# Logomatic-v23.net
KiCad netlist of a schematic drawn in EAGLE
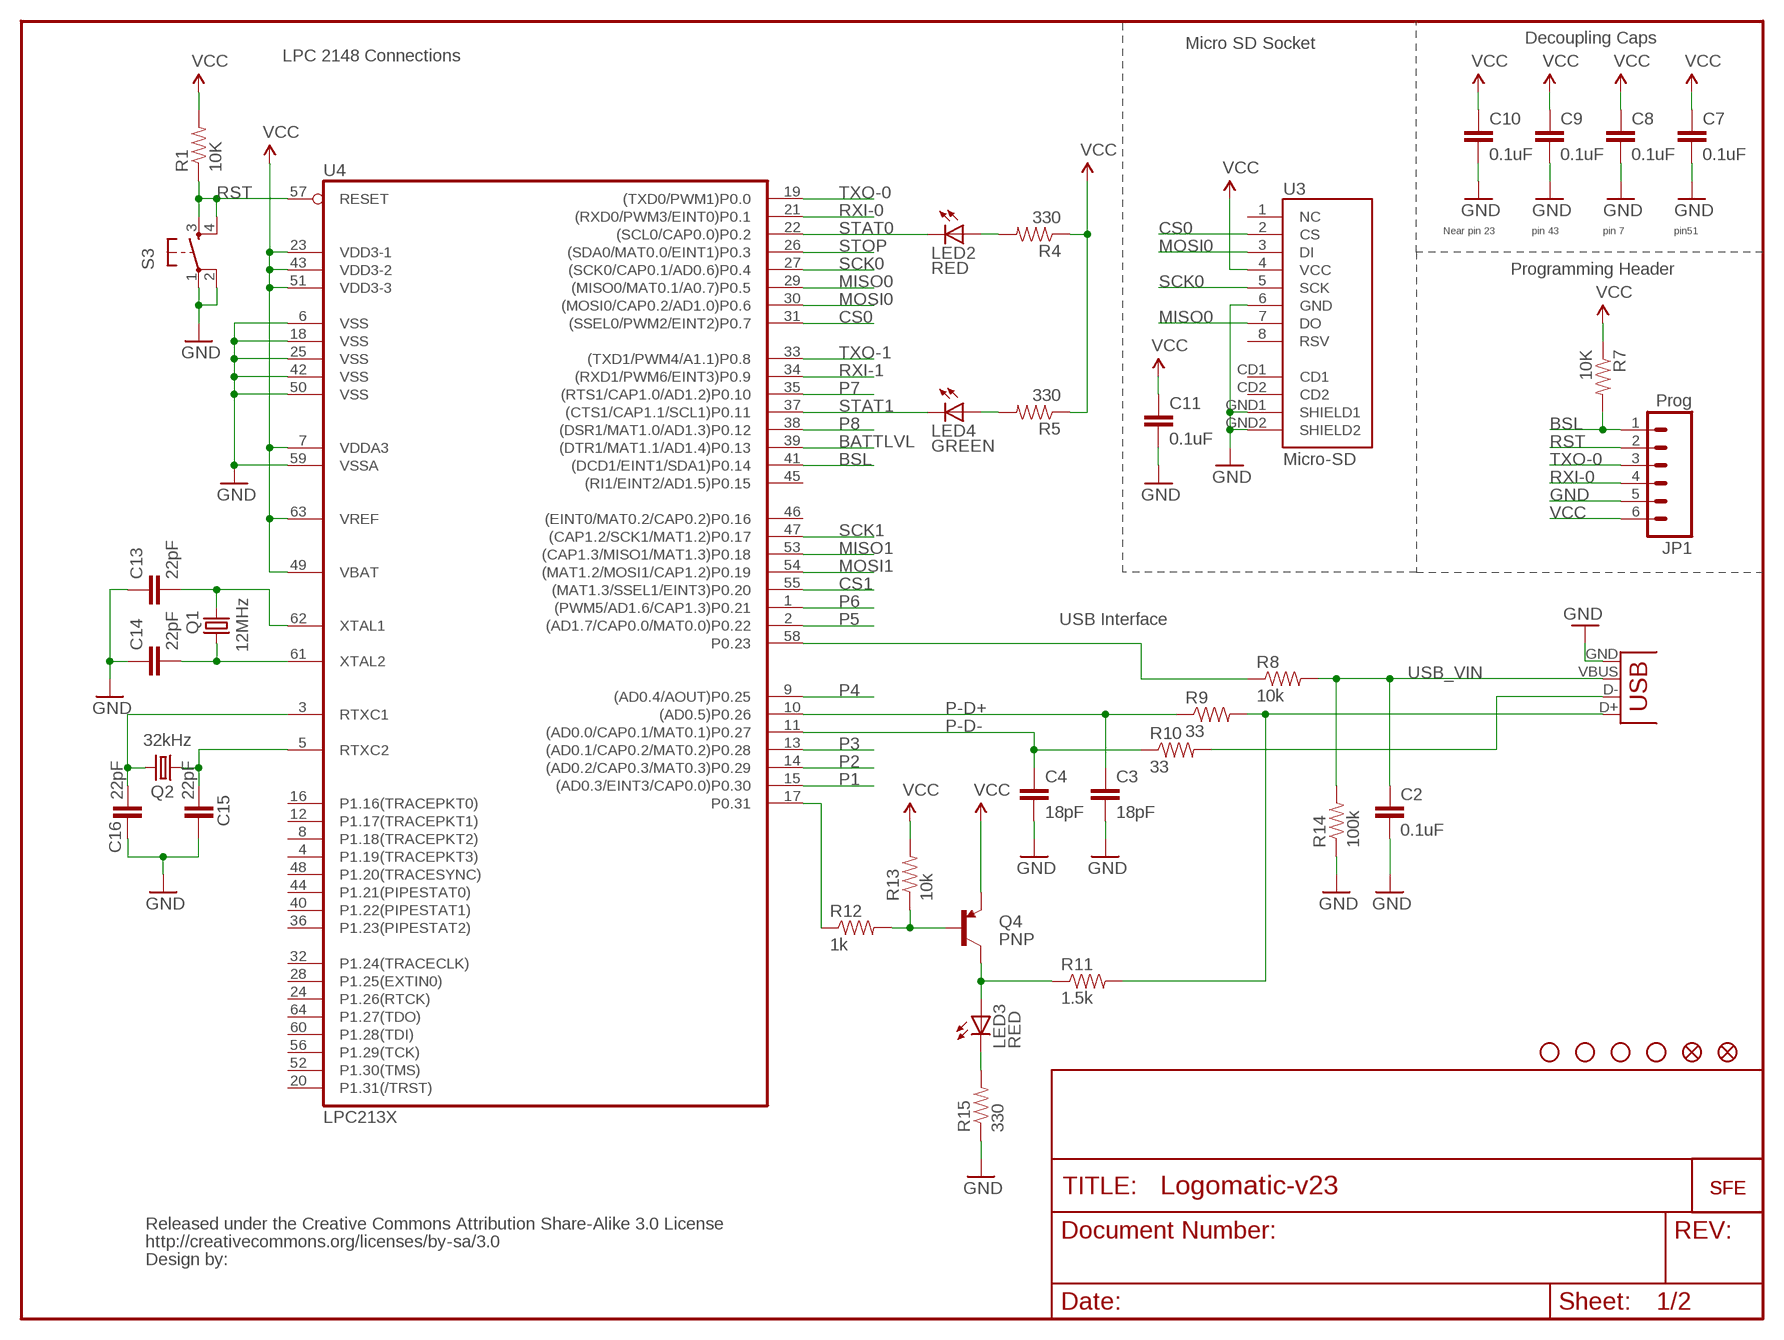
[diagram p0: schematic, sheet 1]
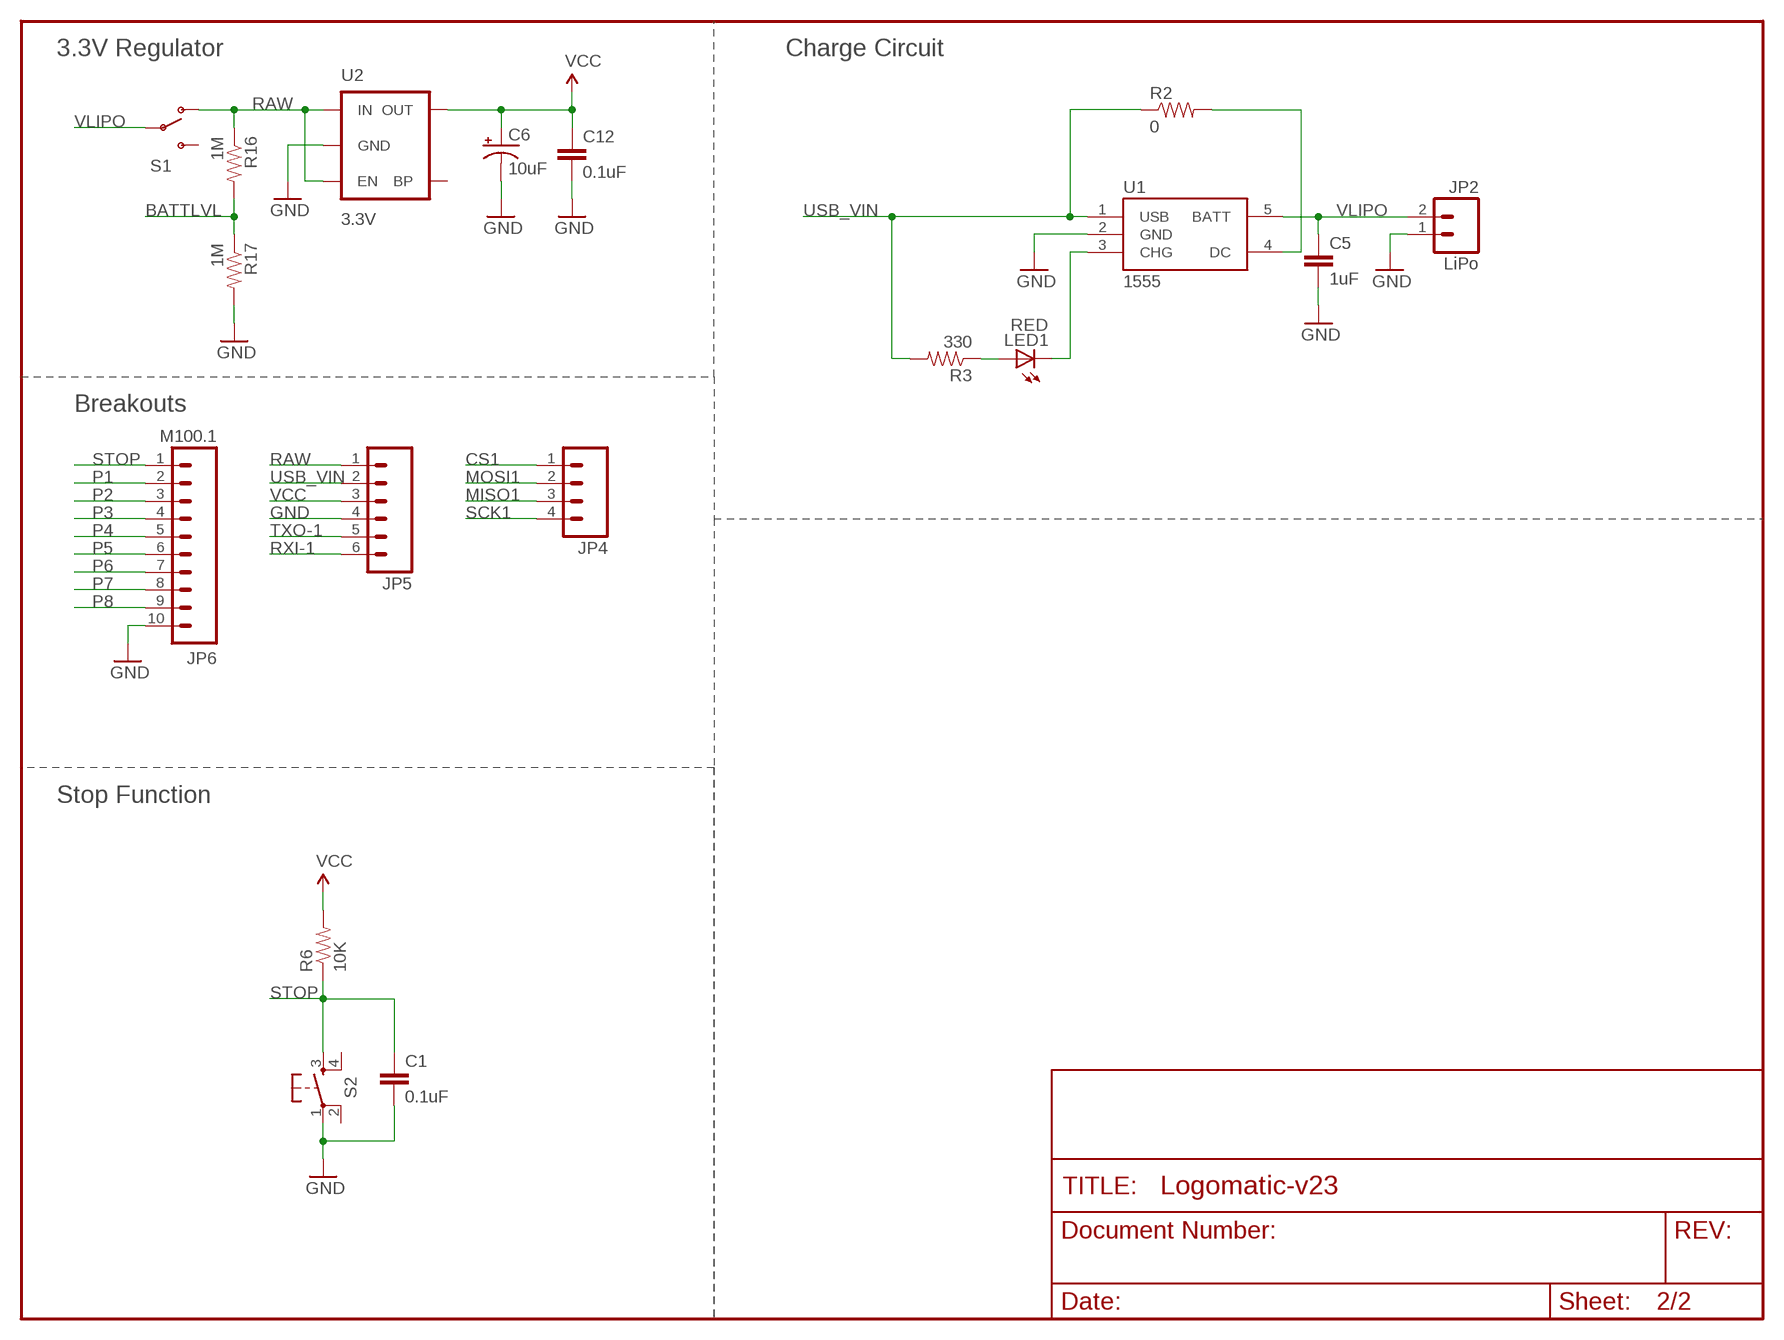
[diagram p1: schematic, sheet 2]

(export (version "E")
  (design (tool "Eeschema 10.0.6"))
  (components
    (comp (ref "C2")
      (value "0.1uF")
      (footprint "eagle-import:C0402")
      (libsource (lib "eagle-import") (part "SparkFunEagle-6-6-07_CAP0402"))
    )
    (comp (ref "C3")
      (value "18pF")
      (footprint "eagle-import:C0402")
      (libsource (lib "eagle-import") (part "SparkFunEagle-6-6-07_CAP0402"))
    )
    (comp (ref "C4")
      (value "18pF")
      (footprint "eagle-import:C0402")
      (libsource (lib "eagle-import") (part "SparkFunEagle-6-6-07_CAP0402"))
    )
    (comp (ref "C7")
      (value "0.1uF")
      (footprint "eagle-import:C0402")
      (libsource (lib "eagle-import") (part "SparkFunEagle-6-6-07_CAP0402"))
    )
    (comp (ref "C8")
      (value "0.1uF")
      (footprint "eagle-import:C0402")
      (libsource (lib "eagle-import") (part "SparkFunEagle-6-6-07_CAP0402"))
    )
    (comp (ref "C9")
      (value "0.1uF")
      (footprint "eagle-import:C0402")
      (libsource (lib "eagle-import") (part "SparkFunEagle-6-6-07_CAP0402"))
    )
    (comp (ref "C10")
      (value "0.1uF")
      (footprint "eagle-import:C0402")
      (libsource (lib "eagle-import") (part "SparkFunEagle-6-6-07_CAP0402"))
    )
    (comp (ref "C11")
      (value "0.1uF")
      (footprint "eagle-import:C0402")
      (libsource (lib "eagle-import") (part "SparkFunEagle-6-6-07_CAP0402"))
    )
    (comp (ref "C13")
      (value "22pF")
      (footprint "eagle-import:C0402")
      (libsource (lib "eagle-import") (part "SparkFunEagle-6-6-07_CAP0402"))
    )
    (comp (ref "C14")
      (value "22pF")
      (footprint "eagle-import:C0402")
      (libsource (lib "eagle-import") (part "SparkFunEagle-6-6-07_CAP0402"))
    )
    (comp (ref "C15")
      (value "22pF")
      (footprint "eagle-import:C0402")
      (libsource (lib "eagle-import") (part "SparkFunEagle-6-6-07_CAP0402"))
    )
    (comp (ref "C16")
      (value "22pF")
      (footprint "eagle-import:C0402")
      (libsource (lib "eagle-import") (part "SparkFunEagle-6-6-07_CAP0402"))
    )
    (comp (ref "JP1")
      (value "Prog")
      (footprint "eagle-import:1X06")
      (libsource (lib "eagle-import") (part "M06SIP"))
    )
    (comp (ref "LED2")
      (value "RED")
      (footprint "eagle-import:LED-0603")
      (libsource (lib "eagle-import") (part "SparkFunEagle-6-6-07_LED0603"))
    )
    (comp (ref "LED3")
      (value "RED")
      (footprint "eagle-import:LED-0603")
      (libsource (lib "eagle-import") (part "SparkFun_Master_LED0603"))
    )
    (comp (ref "LED4")
      (value "GREEN")
      (footprint "eagle-import:LED-0603")
      (libsource (lib "eagle-import") (part "SparkFunEagle-6-6-07_LED0603"))
    )
    (comp (ref "Q1")
      (value "12MHz")
      (footprint "eagle-import:CRYSTAL-SMD-5X3")
      (libsource (lib "eagle-import") (part "SparkFunEagle-6-6-07_CRYSTAL5X3"))
    )
    (comp (ref "Q2")
      (value "32kHz")
      (footprint "eagle-import:CRYSTAL-32KHZ-SMD")
      (libsource (lib "eagle-import") (part "CRYSTAL32-SMD"))
    )
    (comp (ref "Q4")
      (value "PNP")
      (footprint "eagle-import:SOT23-3")
      (libsource (lib "eagle-import") (part "TRANSISTOR_PNPSMD"))
    )
    (comp (ref "R1")
      (value "10K")
      (footprint "eagle-import:C0402")
      (libsource (lib "eagle-import") (part "SparkFunEagle-6-6-07_RESISTOR0402"))
    )
    (comp (ref "R4")
      (value "330")
      (footprint "eagle-import:C0402")
      (libsource (lib "eagle-import") (part "SparkFunEagle-6-6-07_RESISTOR0402"))
    )
    (comp (ref "R5")
      (value "330")
      (footprint "eagle-import:C0402")
      (libsource (lib "eagle-import") (part "SparkFunEagle-6-6-07_RESISTOR0402"))
    )
    (comp (ref "R7")
      (value "10K")
      (footprint "eagle-import:C0402")
      (libsource (lib "eagle-import") (part "SparkFunEagle-6-6-07_RESISTOR0402"))
    )
    (comp (ref "R8")
      (value "10k")
      (footprint "eagle-import:C0402")
      (libsource (lib "eagle-import") (part "SparkFunEagle-6-6-07_RESISTOR0402"))
    )
    (comp (ref "R9")
      (value "33")
      (footprint "eagle-import:C0402")
      (libsource (lib "eagle-import") (part "SparkFunEagle-6-6-07_RESISTOR0402"))
    )
    (comp (ref "R10")
      (value "33")
      (footprint "eagle-import:C0402")
      (libsource (lib "eagle-import") (part "SparkFunEagle-6-6-07_RESISTOR0402"))
    )
    (comp (ref "R11")
      (value "1.5k")
      (footprint "eagle-import:C0402")
      (libsource (lib "eagle-import") (part "SparkFunEagle-6-6-07_RESISTOR0402"))
    )
    (comp (ref "R12")
      (value "1k")
      (footprint "eagle-import:C0402")
      (libsource (lib "eagle-import") (part "SparkFunEagle-6-6-07_RESISTOR0402"))
    )
    (comp (ref "R13")
      (value "10k")
      (footprint "eagle-import:C0402")
      (libsource (lib "eagle-import") (part "SparkFunEagle-6-6-07_RESISTOR0402"))
    )
    (comp (ref "R14")
      (value "100k")
      (footprint "eagle-import:C0402")
      (libsource (lib "eagle-import") (part "SparkFunEagle-6-6-07_RESISTOR0402"))
    )
    (comp (ref "R15")
      (value "330")
      (footprint "eagle-import:C0402")
      (libsource (lib "eagle-import") (part "SparkFunEagle-6-6-07_RESISTOR0402"))
    )
    (comp (ref "S3")
      (value "Reset")
      (footprint "eagle-import:TACTILE_SWITCH_SMD")
      (libsource (lib "eagle-import") (part "TAC_SWITCHSND"))
    )
    (comp (ref "U$1")
      (value "FIDUCIAL1X2")
      (footprint "eagle-import:FIDUCIAL-1X2")
      (libsource (lib "eagle-import") (part "FIDUCIAL1X2"))
    )
    (comp (ref "U$2")
      (value "FIDUCIAL1X2")
      (footprint "eagle-import:FIDUCIAL-1X2")
      (libsource (lib "eagle-import") (part "FIDUCIAL1X2"))
    )
    (comp (ref "U$3")
      (value "STAND-OFF")
      (footprint "eagle-import:STAND-OFF")
      (libsource (lib "eagle-import") (part "STAND-OFF"))
    )
    (comp (ref "U$4")
      (value "STAND-OFF")
      (footprint "eagle-import:STAND-OFF")
      (libsource (lib "eagle-import") (part "STAND-OFF"))
    )
    (comp (ref "U$5")
      (value "STAND-OFF")
      (footprint "eagle-import:STAND-OFF")
      (libsource (lib "eagle-import") (part "STAND-OFF"))
    )
    (comp (ref "U$6")
      (value "LOGO-SFENEW")
      (footprint "eagle-import:SFE-NEW-WEBLOGO")
      (libsource (lib "eagle-import") (part "LOGO-SFENEW"))
    )
    (comp (ref "U$7")
      (value "LOGO-SFESK")
      (footprint "eagle-import:SFE-LOGO-FLAME")
      (libsource (lib "eagle-import") (part "LOGO-SFESK"))
    )
    (comp (ref "U$8")
      (value "STAND-OFF")
      (footprint "eagle-import:STAND-OFF")
      (libsource (lib "eagle-import") (part "STAND-OFF"))
    )
    (comp (ref "U$9")
      (value "CREATIVE_COMMONS")
      (footprint "eagle-import:CREATIVE_COMMONS")
      (libsource (lib "eagle-import") (part "CREATIVE_COMMONS"))
    )
    (comp (ref "U3")
      (value "Micro-SD")
      (footprint "eagle-import:USD-SOCKET-PP")
      (libsource (lib "eagle-import") (part "USD-SOCKETUSD"))
    )
    (comp (ref "U4")
      (value "LPC213X")
      (footprint "eagle-import:SQFP-S-10X10-64")
      (libsource (lib "eagle-import") (part "LPC213X"))
    )
    (comp (ref "X1")
      (value "USBSMD")
      (footprint "eagle-import:USB-MINIB")
      (libsource (lib "eagle-import") (part "USBSMD"))
    )
    (comp (ref "C1")
      (value "0.1uF")
      (footprint "eagle-import:C0402")
      (libsource (lib "eagle-import") (part "SparkFunEagle-6-6-07_CAP0402"))
    )
    (comp (ref "C5")
      (value "1uF")
      (footprint "eagle-import:C0402")
      (libsource (lib "eagle-import") (part "CAP0402"))
    )
    (comp (ref "C6")
      (value "10uF")
      (footprint "eagle-import:EIA3216")
      (libsource (lib "eagle-import") (part "CAP_POL1206"))
    )
    (comp (ref "C12")
      (value "0.1uF")
      (footprint "eagle-import:C0402")
      (libsource (lib "eagle-import") (part "SparkFunEagle-6-6-07_CAP0402"))
    )
    (comp (ref "JP2")
      (value "LiPo")
      (footprint "eagle-import:S2B-PH")
      (libsource (lib "eagle-import") (part "M02-JST-2MM-SMT"))
    )
    (comp (ref "JP4")
      (value "M04PTH")
      (footprint "eagle-import:1X04")
      (libsource (lib "eagle-import") (part "M04PTH"))
    )
    (comp (ref "JP5")
      (value "M06SIP")
      (footprint "eagle-import:1X06")
      (libsource (lib "eagle-import") (part "M06SIP"))
    )
    (comp (ref "JP6")
      (value "M100.1")
      (footprint "eagle-import:1X10")
      (libsource (lib "eagle-import") (part "M100.1"))
    )
    (comp (ref "LED1")
      (value "RED")
      (footprint "eagle-import:LED-0603")
      (libsource (lib "eagle-import") (part "LED0603"))
    )
    (comp (ref "R2")
      (value "0")
      (footprint "eagle-import:C0402")
      (libsource (lib "eagle-import") (part "RESISTOR0402"))
    )
    (comp (ref "R3")
      (value "330")
      (footprint "eagle-import:C0402")
      (libsource (lib "eagle-import") (part "RESISTOR0402"))
    )
    (comp (ref "R6")
      (value "10K")
      (footprint "eagle-import:C0402")
      (libsource (lib "eagle-import") (part "SparkFunEagle-6-6-07_RESISTOR0402"))
    )
    (comp (ref "R16")
      (value "1M")
      (footprint "eagle-import:C0402")
      (libsource (lib "eagle-import") (part "RESISTOR0402"))
    )
    (comp (ref "R17")
      (value "1M")
      (footprint "eagle-import:C0402")
      (libsource (lib "eagle-import") (part "RESISTOR0402"))
    )
    (comp (ref "S1")
      (value "SWITCH-SPSTSMD")
      (footprint "eagle-import:AYZ0202")
      (libsource (lib "eagle-import") (part "SWITCH-SPSTSMD"))
    )
    (comp (ref "S2")
      (value "Stop")
      (footprint "eagle-import:TACTILE_SWITCH_SMD")
      (libsource (lib "eagle-import") (part "TAC_SWITCHSND"))
    )
    (comp (ref "U1")
      (value "1555")
      (footprint "eagle-import:SOT23-5")
      (libsource (lib "eagle-import") (part "MAX1555"))
    )
    (comp (ref "U2")
      (value "3.3V")
      (footprint "eagle-import:SOT23-5")
      (libsource (lib "eagle-import") (part "V_REG_LDOSMD"))
    )
  )
  (nets
    (net (code "1") (name "BATTLVL") (class "Default")
      (node (ref "R16") (pin "2") (pinfunction "2_2") (pintype "passive"))
      (node (ref "R17") (pin "1") (pinfunction "1_1") (pintype "passive"))
      (node (ref "U4") (pin "39") (pinfunction "(DTR1/MAT1.1/AD1.4)P0.13_39") (pintype "bidirectional"))
    )
    (net (code "2") (name "BSL") (class "Default")
      (node (ref "JP1") (pin "1") (pinfunction "1_1") (pintype "passive"))
      (node (ref "R7") (pin "2") (pinfunction "2_2") (pintype "passive"))
      (node (ref "U4") (pin "41") (pinfunction "(DCD1/EINT1/SDA1)P0.14_41") (pintype "bidirectional"))
    )
    (net (code "3") (name "CS0") (class "Default")
      (node (ref "U3") (pin "2") (pinfunction "CS_2") (pintype "bidirectional"))
      (node (ref "U4") (pin "31") (pinfunction "(SSEL0/PWM2/EINT2)P0.7_31") (pintype "bidirectional"))
    )
    (net (code "4") (name "CS1") (class "Default")
      (node (ref "JP4") (pin "1") (pinfunction "1_1") (pintype "passive"))
      (node (ref "U4") (pin "55") (pinfunction "(MAT1.3/SSEL1/EINT3)P0.20_55") (pintype "bidirectional"))
    )
    (net (code "5") (name "GND") (class "Default")
      (node (ref "C1") (pin "2") (pinfunction "2_2") (pintype "passive"))
      (node (ref "C10") (pin "2") (pinfunction "2_2") (pintype "passive"))
      (node (ref "C11") (pin "2") (pinfunction "2_2") (pintype "passive"))
      (node (ref "C12") (pin "2") (pinfunction "2_2") (pintype "passive"))
      (node (ref "C13") (pin "1") (pinfunction "1_1") (pintype "passive"))
      (node (ref "C14") (pin "1") (pinfunction "1_1") (pintype "passive"))
      (node (ref "C15") (pin "1") (pinfunction "1_1") (pintype "passive"))
      (node (ref "C16") (pin "1") (pinfunction "1_1") (pintype "passive"))
      (node (ref "C2") (pin "2") (pinfunction "2_2") (pintype "passive"))
      (node (ref "C3") (pin "2") (pinfunction "2_2") (pintype "passive"))
      (node (ref "C4") (pin "2") (pinfunction "2_2") (pintype "passive"))
      (node (ref "C5") (pin "2") (pinfunction "2_2") (pintype "passive"))
      (node (ref "C6") (pin "C") (pinfunction "-_C") (pintype "passive"))
      (node (ref "C7") (pin "2") (pinfunction "2_2") (pintype "passive"))
      (node (ref "C8") (pin "2") (pinfunction "2_2") (pintype "passive"))
      (node (ref "C9") (pin "2") (pinfunction "2_2") (pintype "passive"))
      (node (ref "JP1") (pin "5") (pinfunction "5_5") (pintype "passive"))
      (node (ref "JP2") (pin "1") (pinfunction "1_1") (pintype "passive"))
      (node (ref "JP5") (pin "4") (pinfunction "4_4") (pintype "passive"))
      (node (ref "JP6") (pin "10") (pinfunction "10_10") (pintype "passive"))
      (node (ref "R14") (pin "1") (pinfunction "1_1") (pintype "passive"))
      (node (ref "R15") (pin "1") (pinfunction "1_1") (pintype "passive"))
      (node (ref "R17") (pin "2") (pinfunction "2_2") (pintype "passive"))
      (node (ref "S2") (pin "1") (pinfunction "1_1") (pintype "passive"))
      (node (ref "S3") (pin "1") (pinfunction "1_1") (pintype "passive"))
      (node (ref "S3") (pin "2") (pinfunction "2_2") (pintype "passive"))
      (node (ref "U1") (pin "2") (pinfunction "GND_2") (pintype "bidirectional"))
      (node (ref "U2") (pin "2") (pinfunction "GND_2") (pintype "input"))
      (node (ref "U3") (pin "6") (pinfunction "GND_6") (pintype "bidirectional"))
      (node (ref "U3") (pin "GND1") (pinfunction "SHIELD1_GND1") (pintype "bidirectional"))
      (node (ref "U3") (pin "GND2") (pinfunction "SHIELD2_GND2") (pintype "bidirectional"))
      (node (ref "U4") (pin "18") (pinfunction "VSS_18") (pintype "power_in"))
      (node (ref "U4") (pin "25") (pinfunction "VSS_25") (pintype "power_in"))
      (node (ref "U4") (pin "42") (pinfunction "VSS_42") (pintype "power_in"))
      (node (ref "U4") (pin "50") (pinfunction "VSS_50") (pintype "power_in"))
      (node (ref "U4") (pin "59") (pinfunction "VSSA_59") (pintype "power_in"))
      (node (ref "U4") (pin "6") (pinfunction "VSS_6") (pintype "power_in"))
      (node (ref "X1") (pin "GND") (pinfunction "GND_GND") (pintype "bidirectional"))
    )
    (net (code "6") (name "MISO0") (class "Default")
      (node (ref "U3") (pin "7") (pinfunction "DO_7") (pintype "bidirectional"))
      (node (ref "U4") (pin "29") (pinfunction "(MISO0/MAT0.1/A0.7)P0.5_29") (pintype "bidirectional"))
    )
    (net (code "7") (name "MISO1") (class "Default")
      (node (ref "JP4") (pin "3") (pinfunction "3_3") (pintype "passive"))
      (node (ref "U4") (pin "53") (pinfunction "(CAP1.3/MISO1/MAT1.3)P0.18_53") (pintype "bidirectional"))
    )
    (net (code "8") (name "MOSI0") (class "Default")
      (node (ref "U3") (pin "3") (pinfunction "DI_3") (pintype "bidirectional"))
      (node (ref "U4") (pin "30") (pinfunction "(MOSI0/CAP0.2/AD1.0)P0.6_30") (pintype "bidirectional"))
    )
    (net (code "9") (name "MOSI1") (class "Default")
      (node (ref "JP4") (pin "2") (pinfunction "2_2") (pintype "passive"))
      (node (ref "U4") (pin "54") (pinfunction "(MAT1.2/MOSI1/CAP1.2)P0.19_54") (pintype "bidirectional"))
    )
    (net (code "10") (name "Net-(LED1-PadA)") (class "Default")
      (node (ref "LED1") (pin "A") (pinfunction "A_A") (pintype "passive"))
      (node (ref "R3") (pin "1") (pinfunction "1_1") (pintype "passive"))
    )
    (net (code "11") (name "Net-(LED2-PadA)") (class "Default")
      (node (ref "LED2") (pin "A") (pinfunction "A_A") (pintype "passive"))
      (node (ref "R4") (pin "2") (pinfunction "2_2") (pintype "passive"))
    )
    (net (code "12") (name "Net-(LED3-PadC)") (class "Default")
      (node (ref "LED3") (pin "C") (pinfunction "C_C") (pintype "passive"))
      (node (ref "R15") (pin "2") (pinfunction "2_2") (pintype "passive"))
    )
    (net (code "13") (name "Net-(LED4-PadA)") (class "Default")
      (node (ref "LED4") (pin "A") (pinfunction "A_A") (pintype "passive"))
      (node (ref "R5") (pin "2") (pinfunction "2_2") (pintype "passive"))
    )
    (net (code "14") (name "Net-(Q1-2)") (class "Default")
      (node (ref "C13") (pin "2") (pinfunction "2_2") (pintype "passive"))
      (node (ref "Q1") (pin "3") (pinfunction "2_3") (pintype "passive"))
      (node (ref "U4") (pin "62") (pinfunction "XTAL1_62") (pintype "input"))
    )
    (net (code "15") (name "Net-(Q2-1)") (class "Default")
      (node (ref "C15") (pin "2") (pinfunction "2_2") (pintype "passive"))
      (node (ref "Q2") (pin "X1") (pinfunction "1_X1") (pintype "passive"))
      (node (ref "U4") (pin "5") (pinfunction "RTXC2_5") (pintype "output"))
    )
    (net (code "16") (name "Net-(Q2-2)") (class "Default")
      (node (ref "C16") (pin "2") (pinfunction "2_2") (pintype "passive"))
      (node (ref "Q2") (pin "X2") (pinfunction "2_X2") (pintype "passive"))
      (node (ref "U4") (pin "3") (pinfunction "RTXC1_3") (pintype "input"))
    )
    (net (code "17") (name "Net-(Q4-B)") (class "Default")
      (node (ref "Q4") (pin "1") (pinfunction "B_1") (pintype "passive"))
      (node (ref "R12") (pin "2") (pinfunction "2_2") (pintype "passive"))
      (node (ref "R13") (pin "1") (pinfunction "1_1") (pintype "passive"))
    )
    (net (code "18") (name "Net-(Q4-C)") (class "Default")
      (node (ref "LED3") (pin "A") (pinfunction "A_A") (pintype "passive"))
      (node (ref "Q4") (pin "3") (pinfunction "C_3") (pintype "passive"))
      (node (ref "R11") (pin "1") (pinfunction "1_1") (pintype "passive"))
    )
    (net (code "19") (name "Net-(R10-Pad2)") (class "Default")
      (node (ref "R10") (pin "2") (pinfunction "2_2") (pintype "passive"))
      (node (ref "X1") (pin "D-") (pinfunction "D-_D-") (pintype "bidirectional"))
    )
    (net (code "20") (name "Net-(R11-Pad2)") (class "Default")
      (node (ref "R11") (pin "2") (pinfunction "2_2") (pintype "passive"))
      (node (ref "R9") (pin "2") (pinfunction "2_2") (pintype "passive"))
      (node (ref "X1") (pin "D+") (pinfunction "D+_D+") (pintype "bidirectional"))
    )
    (net (code "21") (name "Net-(U1-CHG)") (class "Default")
      (node (ref "LED1") (pin "C") (pinfunction "C_C") (pintype "passive"))
      (node (ref "U1") (pin "3") (pinfunction "CHG_3") (pintype "bidirectional"))
    )
    (net (code "22") (name "Net-(U1-DC)") (class "Default")
      (node (ref "R2") (pin "2") (pinfunction "2_2") (pintype "passive"))
      (node (ref "U1") (pin "4") (pinfunction "DC_4") (pintype "bidirectional"))
    )
    (net (code "23") (name "Net-(U4-P0.23)") (class "Default")
      (node (ref "R8") (pin "1") (pinfunction "1_1") (pintype "passive"))
      (node (ref "U4") (pin "58") (pinfunction "P0.23_58") (pintype "bidirectional"))
    )
    (net (code "24") (name "Net-(U4-P0.31)") (class "Default")
      (node (ref "R12") (pin "1") (pinfunction "1_1") (pintype "passive"))
      (node (ref "U4") (pin "17") (pinfunction "P0.31_17") (pintype "output"))
    )
    (net (code "25") (name "Net-(U4-XTAL2)") (class "Default")
      (node (ref "C14") (pin "2") (pinfunction "2_2") (pintype "passive"))
      (node (ref "Q1") (pin "1") (pinfunction "1_1") (pintype "passive"))
      (node (ref "U4") (pin "61") (pinfunction "XTAL2_61") (pintype "output"))
    )
    (net (code "26") (name "P-D+") (class "Default")
      (node (ref "C3") (pin "1") (pinfunction "1_1") (pintype "passive"))
      (node (ref "R9") (pin "1") (pinfunction "1_1") (pintype "passive"))
      (node (ref "U4") (pin "10") (pinfunction "(AD0.5)P0.26_10") (pintype "bidirectional"))
    )
    (net (code "27") (name "P-D-") (class "Default")
      (node (ref "C4") (pin "1") (pinfunction "1_1") (pintype "passive"))
      (node (ref "R10") (pin "1") (pinfunction "1_1") (pintype "passive"))
      (node (ref "U4") (pin "11") (pinfunction "(AD0.0/CAP0.1/MAT0.1)P0.27_11") (pintype "bidirectional"))
    )
    (net (code "28") (name "P1") (class "Default")
      (node (ref "JP6") (pin "2") (pinfunction "2_2") (pintype "passive"))
      (node (ref "U4") (pin "15") (pinfunction "(AD0.3/EINT3/CAP0.0)P0.30_15") (pintype "bidirectional"))
    )
    (net (code "29") (name "P2") (class "Default")
      (node (ref "JP6") (pin "3") (pinfunction "3_3") (pintype "passive"))
      (node (ref "U4") (pin "14") (pinfunction "(AD0.2/CAP0.3/MAT0.3)P0.29_14") (pintype "bidirectional"))
    )
    (net (code "30") (name "P3") (class "Default")
      (node (ref "JP6") (pin "4") (pinfunction "4_4") (pintype "passive"))
      (node (ref "U4") (pin "13") (pinfunction "(AD0.1/CAP0.2/MAT0.2)P0.28_13") (pintype "bidirectional"))
    )
    (net (code "31") (name "P4") (class "Default")
      (node (ref "JP6") (pin "5") (pinfunction "5_5") (pintype "passive"))
      (node (ref "U4") (pin "9") (pinfunction "(AD0.4/AOUT)P0.25_9") (pintype "bidirectional"))
    )
    (net (code "32") (name "P5") (class "Default")
      (node (ref "JP6") (pin "6") (pinfunction "6_6") (pintype "passive"))
      (node (ref "U4") (pin "2") (pinfunction "(AD1.7/CAP0.0/MAT0.0)P0.22_2") (pintype "bidirectional"))
    )
    (net (code "33") (name "P6") (class "Default")
      (node (ref "JP6") (pin "7") (pinfunction "7_7") (pintype "passive"))
      (node (ref "U4") (pin "1") (pinfunction "(PWM5/AD1.6/CAP1.3)P0.21_1") (pintype "bidirectional"))
    )
    (net (code "34") (name "P7") (class "Default")
      (node (ref "JP6") (pin "8") (pinfunction "8_8") (pintype "passive"))
      (node (ref "U4") (pin "35") (pinfunction "(RTS1/CAP1.0/AD1.2)P0.10_35") (pintype "bidirectional"))
    )
    (net (code "35") (name "P8") (class "Default")
      (node (ref "JP6") (pin "9") (pinfunction "9_9") (pintype "passive"))
      (node (ref "U4") (pin "38") (pinfunction "(DSR1/MAT1.0/AD1.3)P0.12_38") (pintype "bidirectional"))
    )
    (net (code "36") (name "RAW") (class "Default")
      (node (ref "JP5") (pin "1") (pinfunction "1_1") (pintype "passive"))
      (node (ref "R16") (pin "1") (pinfunction "1_1") (pintype "passive"))
      (node (ref "S1") (pin "1") (pinfunction "O_1") (pintype "passive"))
      (node (ref "U2") (pin "1") (pinfunction "IN_1") (pintype "input"))
      (node (ref "U2") (pin "3") (pinfunction "EN_3") (pintype "input"))
    )
    (net (code "37") (name "RST") (class "Default")
      (node (ref "JP1") (pin "2") (pinfunction "2_2") (pintype "passive"))
      (node (ref "R1") (pin "1") (pinfunction "1_1") (pintype "passive"))
      (node (ref "S3") (pin "3") (pinfunction "3_3") (pintype "passive"))
      (node (ref "S3") (pin "4") (pinfunction "4_4") (pintype "passive"))
      (node (ref "U4") (pin "57") (pinfunction "RESET_57") (pintype "input"))
    )
    (net (code "38") (name "RXI-0") (class "Default")
      (node (ref "JP1") (pin "4") (pinfunction "4_4") (pintype "passive"))
      (node (ref "U4") (pin "21") (pinfunction "(RXD0/PWM3/EINT0)P0.1_21") (pintype "bidirectional"))
    )
    (net (code "39") (name "RXI-1") (class "Default")
      (node (ref "JP5") (pin "6") (pinfunction "6_6") (pintype "passive"))
      (node (ref "U4") (pin "34") (pinfunction "(RXD1/PWM6/EINT3)P0.9_34") (pintype "bidirectional"))
    )
    (net (code "40") (name "SCK0") (class "Default")
      (node (ref "U3") (pin "5") (pinfunction "SCK_5") (pintype "bidirectional"))
      (node (ref "U4") (pin "27") (pinfunction "(SCK0/CAP0.1/AD0.6)P0.4_27") (pintype "bidirectional"))
    )
    (net (code "41") (name "SCK1") (class "Default")
      (node (ref "JP4") (pin "4") (pinfunction "4_4") (pintype "passive"))
      (node (ref "U4") (pin "47") (pinfunction "(CAP1.2/SCK1/MAT1.2)P0.17_47") (pintype "bidirectional"))
    )
    (net (code "42") (name "STAT0") (class "Default")
      (node (ref "LED2") (pin "C") (pinfunction "C_C") (pintype "passive"))
      (node (ref "U4") (pin "22") (pinfunction "(SCL0/CAP0.0)P0.2_22") (pintype "bidirectional"))
    )
    (net (code "43") (name "STAT1") (class "Default")
      (node (ref "LED4") (pin "C") (pinfunction "C_C") (pintype "passive"))
      (node (ref "U4") (pin "37") (pinfunction "(CTS1/CAP1.1/SCL1)P0.11_37") (pintype "bidirectional"))
    )
    (net (code "44") (name "STOP") (class "Default")
      (node (ref "C1") (pin "1") (pinfunction "1_1") (pintype "passive"))
      (node (ref "JP6") (pin "1") (pinfunction "1_1") (pintype "passive"))
      (node (ref "R6") (pin "1") (pinfunction "1_1") (pintype "passive"))
      (node (ref "S2") (pin "3") (pinfunction "3_3") (pintype "passive"))
      (node (ref "U4") (pin "26") (pinfunction "(SDA0/MAT0.0/EINT1)P0.3_26") (pintype "bidirectional"))
    )
    (net (code "45") (name "TXO-0") (class "Default")
      (node (ref "JP1") (pin "3") (pinfunction "3_3") (pintype "passive"))
      (node (ref "U4") (pin "19") (pinfunction "(TXD0/PWM1)P0.0_19") (pintype "bidirectional"))
    )
    (net (code "46") (name "TXO-1") (class "Default")
      (node (ref "JP5") (pin "5") (pinfunction "5_5") (pintype "passive"))
      (node (ref "U4") (pin "33") (pinfunction "(TXD1/PWM4/A1.1)P0.8_33") (pintype "bidirectional"))
    )
    (net (code "47") (name "USB_VIN") (class "Default")
      (node (ref "C2") (pin "1") (pinfunction "1_1") (pintype "passive"))
      (node (ref "JP5") (pin "2") (pinfunction "2_2") (pintype "passive"))
      (node (ref "R14") (pin "2") (pinfunction "2_2") (pintype "passive"))
      (node (ref "R2") (pin "1") (pinfunction "1_1") (pintype "passive"))
      (node (ref "R3") (pin "2") (pinfunction "2_2") (pintype "passive"))
      (node (ref "R8") (pin "2") (pinfunction "2_2") (pintype "passive"))
      (node (ref "U1") (pin "1") (pinfunction "USB_1") (pintype "bidirectional"))
      (node (ref "X1") (pin "VBUS") (pinfunction "VBUS_VBUS") (pintype "bidirectional"))
    )
    (net (code "48") (name "VCC") (class "Default")
      (node (ref "C10") (pin "1") (pinfunction "1_1") (pintype "passive"))
      (node (ref "C11") (pin "1") (pinfunction "1_1") (pintype "passive"))
      (node (ref "C12") (pin "1") (pinfunction "1_1") (pintype "passive"))
      (node (ref "C6") (pin "A") (pinfunction "+_A") (pintype "passive"))
      (node (ref "C7") (pin "1") (pinfunction "1_1") (pintype "passive"))
      (node (ref "C8") (pin "1") (pinfunction "1_1") (pintype "passive"))
      (node (ref "C9") (pin "1") (pinfunction "1_1") (pintype "passive"))
      (node (ref "JP1") (pin "6") (pinfunction "6_6") (pintype "passive"))
      (node (ref "JP5") (pin "3") (pinfunction "3_3") (pintype "passive"))
      (node (ref "Q4") (pin "2") (pinfunction "E_2") (pintype "passive"))
      (node (ref "R1") (pin "2") (pinfunction "2_2") (pintype "passive"))
      (node (ref "R13") (pin "2") (pinfunction "2_2") (pintype "passive"))
      (node (ref "R4") (pin "1") (pinfunction "1_1") (pintype "passive"))
      (node (ref "R5") (pin "1") (pinfunction "1_1") (pintype "passive"))
      (node (ref "R6") (pin "2") (pinfunction "2_2") (pintype "passive"))
      (node (ref "R7") (pin "1") (pinfunction "1_1") (pintype "passive"))
      (node (ref "U2") (pin "5") (pinfunction "OUT_5") (pintype "passive"))
      (node (ref "U3") (pin "4") (pinfunction "VCC_4") (pintype "bidirectional"))
      (node (ref "U4") (pin "23") (pinfunction "VDD3-1_23") (pintype "power_in"))
      (node (ref "U4") (pin "43") (pinfunction "VDD3-2_43") (pintype "power_in"))
      (node (ref "U4") (pin "49") (pinfunction "VBAT_49") (pintype "power_in"))
      (node (ref "U4") (pin "51") (pinfunction "VDD3-3_51") (pintype "power_in"))
      (node (ref "U4") (pin "63") (pinfunction "VREF_63") (pintype "input"))
      (node (ref "U4") (pin "7") (pinfunction "VDDA3_7") (pintype "power_in"))
    )
    (net (code "49") (name "VLIPO") (class "Default")
      (node (ref "C5") (pin "1") (pinfunction "1_1") (pintype "passive"))
      (node (ref "JP2") (pin "2") (pinfunction "2_2") (pintype "passive"))
      (node (ref "S1") (pin "2") (pinfunction "P_2") (pintype "passive"))
      (node (ref "U1") (pin "5") (pinfunction "BATT_5") (pintype "bidirectional"))
    )
    (net (code "50") (name "unconnected-(S1-S-Pad3)") (class "Default")
      (node (ref "S1") (pin "3") (pinfunction "S_3") (pintype "passive"))
    )
    (net (code "51") (name "unconnected-(S2-Pad2)") (class "Default")
      (node (ref "S2") (pin "2") (pinfunction "2_2") (pintype "passive"))
    )
    (net (code "52") (name "unconnected-(S2-Pad4)") (class "Default")
      (node (ref "S2") (pin "4") (pinfunction "4_4") (pintype "passive"))
    )
    (net (code "53") (name "unconnected-(U2-BP-Pad4)") (class "Default")
      (node (ref "U2") (pin "4") (pinfunction "BP_4") (pintype "input"))
    )
    (net (code "54") (name "unconnected-(U3-NC-Pad1)") (class "Default")
      (node (ref "U3") (pin "1") (pinfunction "NC_1") (pintype "bidirectional"))
    )
    (net (code "55") (name "unconnected-(U3-PadCD1)") (class "Default")
      (node (ref "U3") (pin "CD1") (pinfunction "CD1_CD1") (pintype "bidirectional"))
    )
    (net (code "56") (name "unconnected-(U3-PadCD2)") (class "Default")
      (node (ref "U3") (pin "CD2") (pinfunction "CD2_CD2") (pintype "bidirectional"))
    )
    (net (code "57") (name "unconnected-(U3-RSV-Pad8)") (class "Default")
      (node (ref "U3") (pin "8") (pinfunction "RSV_8") (pintype "bidirectional"))
    )
    (net (code "58") (name "unconnected-(U4-(EINT0{slash}MAT0.2{slash}CAP0.2)P0.16-Pad46)") (class "Default")
      (node (ref "U4") (pin "46") (pinfunction "(EINT0/MAT0.2/CAP0.2)P0.16_46") (pintype "bidirectional"))
    )
    (net (code "59") (name "unconnected-(U4-(RI1{slash}EINT2{slash}AD1.5)P0.15-Pad45)") (class "Default")
      (node (ref "U4") (pin "45") (pinfunction "(RI1/EINT2/AD1.5)P0.15_45") (pintype "bidirectional"))
    )
    (net (code "60") (name "unconnected-(U4-P1.16(TRACEPKT0)-Pad16)") (class "Default")
      (node (ref "U4") (pin "16") (pinfunction "P1.16(TRACEPKT0)_16") (pintype "bidirectional"))
    )
    (net (code "61") (name "unconnected-(U4-P1.17(TRACEPKT1)-Pad12)") (class "Default")
      (node (ref "U4") (pin "12") (pinfunction "P1.17(TRACEPKT1)_12") (pintype "bidirectional"))
    )
    (net (code "62") (name "unconnected-(U4-P1.18(TRACEPKT2)-Pad8)") (class "Default")
      (node (ref "U4") (pin "8") (pinfunction "P1.18(TRACEPKT2)_8") (pintype "bidirectional"))
    )
    (net (code "63") (name "unconnected-(U4-P1.19(TRACEPKT3)-Pad4)") (class "Default")
      (node (ref "U4") (pin "4") (pinfunction "P1.19(TRACEPKT3)_4") (pintype "bidirectional"))
    )
    (net (code "64") (name "unconnected-(U4-P1.20(TRACESYNC)-Pad48)") (class "Default")
      (node (ref "U4") (pin "48") (pinfunction "P1.20(TRACESYNC)_48") (pintype "bidirectional"))
    )
    (net (code "65") (name "unconnected-(U4-P1.21(PIPESTAT0)-Pad44)") (class "Default")
      (node (ref "U4") (pin "44") (pinfunction "P1.21(PIPESTAT0)_44") (pintype "bidirectional"))
    )
    (net (code "66") (name "unconnected-(U4-P1.22(PIPESTAT1)-Pad40)") (class "Default")
      (node (ref "U4") (pin "40") (pinfunction "P1.22(PIPESTAT1)_40") (pintype "bidirectional"))
    )
    (net (code "67") (name "unconnected-(U4-P1.23(PIPESTAT2)-Pad36)") (class "Default")
      (node (ref "U4") (pin "36") (pinfunction "P1.23(PIPESTAT2)_36") (pintype "bidirectional"))
    )
    (net (code "68") (name "unconnected-(U4-P1.24(TRACECLK)-Pad32)") (class "Default")
      (node (ref "U4") (pin "32") (pinfunction "P1.24(TRACECLK)_32") (pintype "bidirectional"))
    )
    (net (code "69") (name "unconnected-(U4-P1.25(EXTIN0)-Pad28)") (class "Default")
      (node (ref "U4") (pin "28") (pinfunction "P1.25(EXTIN0)_28") (pintype "bidirectional"))
    )
    (net (code "70") (name "unconnected-(U4-P1.26(RTCK)-Pad24)") (class "Default")
      (node (ref "U4") (pin "24") (pinfunction "P1.26(RTCK)_24") (pintype "bidirectional"))
    )
    (net (code "71") (name "unconnected-(U4-P1.27(TDO)-Pad64)") (class "Default")
      (node (ref "U4") (pin "64") (pinfunction "P1.27(TDO)_64") (pintype "bidirectional"))
    )
    (net (code "72") (name "unconnected-(U4-P1.28(TDI)-Pad60)") (class "Default")
      (node (ref "U4") (pin "60") (pinfunction "P1.28(TDI)_60") (pintype "bidirectional"))
    )
    (net (code "73") (name "unconnected-(U4-P1.29(TCK)-Pad56)") (class "Default")
      (node (ref "U4") (pin "56") (pinfunction "P1.29(TCK)_56") (pintype "bidirectional"))
    )
    (net (code "74") (name "unconnected-(U4-P1.30(TMS)-Pad52)") (class "Default")
      (node (ref "U4") (pin "52") (pinfunction "P1.30(TMS)_52") (pintype "bidirectional"))
    )
    (net (code "75") (name "unconnected-(U4-P1.31({slash}TRST)-Pad20)") (class "Default")
      (node (ref "U4") (pin "20") (pinfunction "P1.31(/TRST)_20") (pintype "bidirectional"))
    )
  )
)
